# 12e.net
KiCad netlist of a schematic drawn in EAGLE
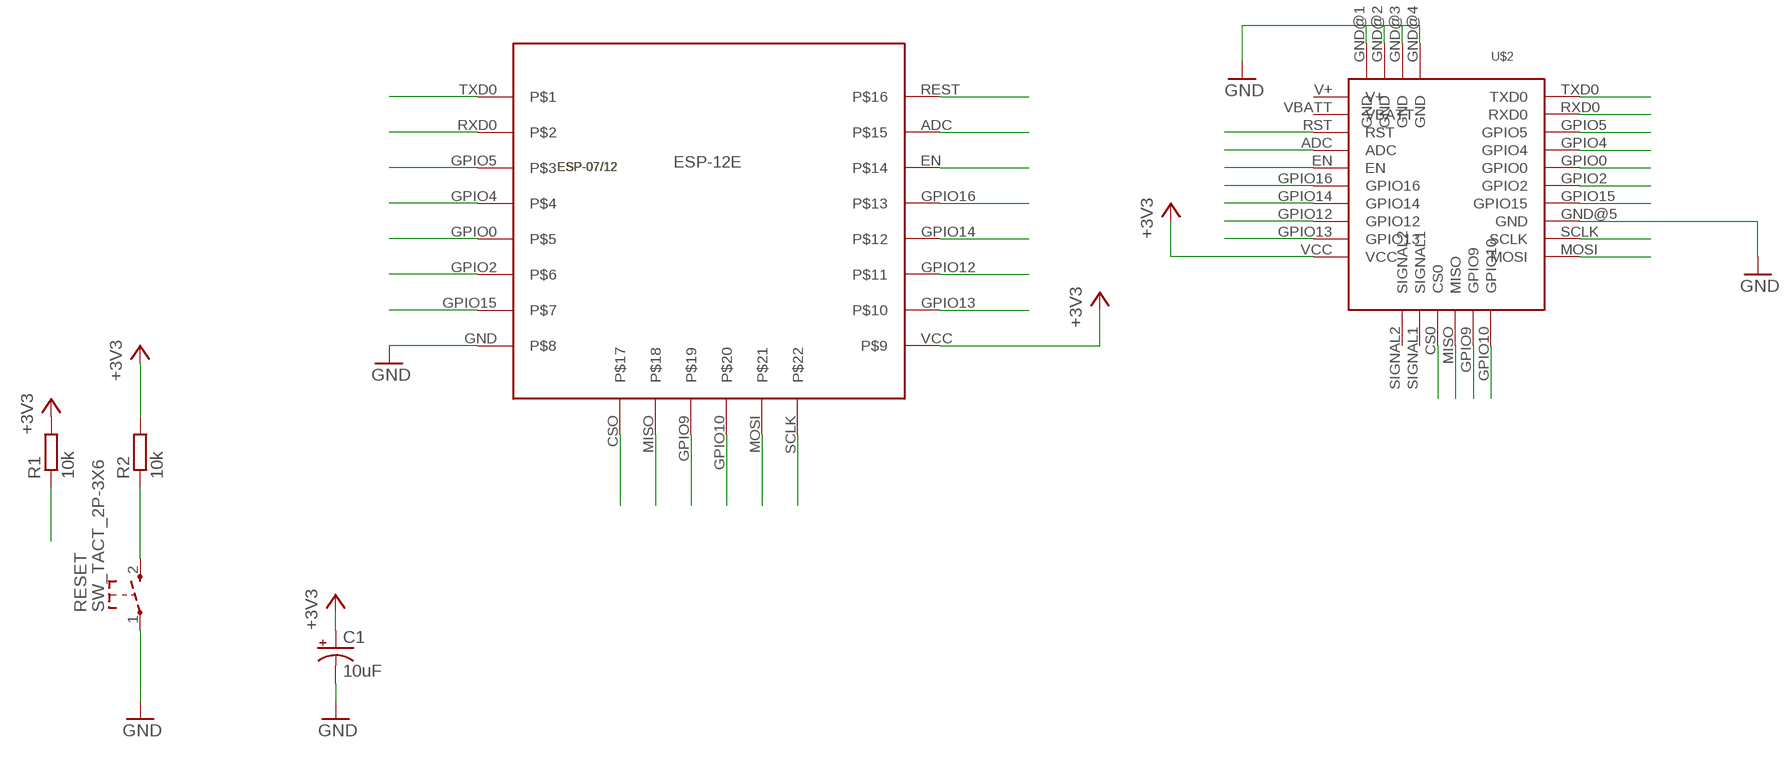
[diagram p0: schematic, sheet 1]

(export (version "E")
  (design (tool "Eeschema 10.0.6"))
  (components
    (comp (ref "C1")
      (value "10uF")
      (footprint "eagle-import:EIA3216")
      (libsource (lib "eagle-import") (part "10UF-16V-10%(TANT)"))
    )
    (comp (ref "R1")
      (value "10k")
      (footprint "eagle-import:R1206")
      (libsource (lib "eagle-import") (part "RESISTOR-1206"))
    )
    (comp (ref "R2")
      (value "10k")
      (footprint "eagle-import:R1206")
      (libsource (lib "eagle-import") (part "RESISTOR-1206"))
    )
    (comp (ref "RESET")
      (value "SW_TACT_2P-3X6")
      (footprint "eagle-import:SW_TACT_3X6")
      (libsource (lib "eagle-import") (part "SW_TACT_2P-3X6"))
    )
    (comp (ref "U$1")
      (value "ESP-07/12_ESP-12E")
      (footprint "eagle-import:ESP-07_12")
      (libsource (lib "eagle-import") (part "ESP-07/12_ESP-12E"))
    )
    (comp (ref "U$2")
      (value "ESP-BOARD")
      (footprint "eagle-import:ESP-BOARD")
      (libsource (lib "eagle-import") (part "ESP-BOARD"))
    )
  )
  (nets
    (net (code "1") (name "+3V3") (class "Default")
      (node (ref "C1") (pin "A") (pinfunction "+_A") (pintype "passive"))
      (node (ref "R1") (pin "2") (pinfunction "2_2") (pintype "passive"))
      (node (ref "R2") (pin "2") (pinfunction "2_2") (pintype "passive"))
      (node (ref "U$1") (pin "VCC") (pinfunction "P$9_VCC") (pintype "bidirectional"))
      (node (ref "U$2") (pin "VCC") (pinfunction "VCC_VCC") (pintype "power_in"))
    )
    (net (code "2") (name "/ADC") (class "Default")
      (node (ref "U$1") (pin "ADC") (pinfunction "P$15_ADC") (pintype "bidirectional"))
      (node (ref "U$2") (pin "ADC") (pinfunction "ADC_ADC") (pintype "bidirectional"))
    )
    (net (code "3") (name "/CS0") (class "Default")
      (node (ref "U$1") (pin "CSO") (pinfunction "P$17_CSO") (pintype "bidirectional"))
      (node (ref "U$2") (pin "CS0") (pinfunction "CS0_CS0") (pintype "bidirectional"))
    )
    (net (code "4") (name "/EN") (class "Default")
      (node (ref "R1") (pin "1") (pinfunction "1_1") (pintype "passive"))
      (node (ref "U$1") (pin "EN") (pinfunction "P$14_EN") (pintype "bidirectional"))
      (node (ref "U$2") (pin "EN") (pinfunction "EN_EN") (pintype "bidirectional"))
    )
    (net (code "5") (name "/GPIO0") (class "Default")
      (node (ref "U$1") (pin "GPIO0") (pinfunction "P$5_GPIO0") (pintype "bidirectional"))
      (node (ref "U$2") (pin "GPIO0") (pinfunction "GPIO0_GPIO0") (pintype "bidirectional"))
    )
    (net (code "6") (name "/GPIO2") (class "Default")
      (node (ref "U$1") (pin "GPIO2") (pinfunction "P$6_GPIO2") (pintype "bidirectional"))
      (node (ref "U$2") (pin "GPIO2") (pinfunction "GPIO2_GPIO2") (pintype "bidirectional"))
    )
    (net (code "7") (name "/GPIO4") (class "Default")
      (node (ref "U$1") (pin "GPIO4") (pinfunction "P$4_GPIO4") (pintype "bidirectional"))
      (node (ref "U$2") (pin "GPIO4") (pinfunction "GPIO4_GPIO4") (pintype "bidirectional"))
    )
    (net (code "8") (name "/GPIO5") (class "Default")
      (node (ref "U$1") (pin "GPIO5") (pinfunction "P$3_GPIO5") (pintype "bidirectional"))
      (node (ref "U$2") (pin "GPIO5") (pinfunction "GPIO5_GPIO5") (pintype "bidirectional"))
    )
    (net (code "9") (name "/GPIO9") (class "Default")
      (node (ref "U$1") (pin "GPIO9") (pinfunction "P$19_GPIO9") (pintype "bidirectional"))
      (node (ref "U$2") (pin "GPIO9") (pinfunction "GPIO9_GPIO9") (pintype "bidirectional"))
    )
    (net (code "10") (name "/GPIO10") (class "Default")
      (node (ref "U$1") (pin "GPIO10") (pinfunction "P$20_GPIO10") (pintype "bidirectional"))
      (node (ref "U$2") (pin "GPIO10") (pinfunction "GPIO10_GPIO10") (pintype "bidirectional"))
    )
    (net (code "11") (name "/GPIO12") (class "Default")
      (node (ref "U$1") (pin "GPIO12") (pinfunction "P$11_GPIO12") (pintype "bidirectional"))
      (node (ref "U$2") (pin "GPIO12") (pinfunction "GPIO12_GPIO12") (pintype "bidirectional"))
    )
    (net (code "12") (name "/GPIO13") (class "Default")
      (node (ref "U$1") (pin "GPIO13") (pinfunction "P$10_GPIO13") (pintype "bidirectional"))
      (node (ref "U$2") (pin "GPIO13") (pinfunction "GPIO13_GPIO13") (pintype "bidirectional"))
    )
    (net (code "13") (name "/GPIO14") (class "Default")
      (node (ref "U$1") (pin "GPIO14") (pinfunction "P$12_GPIO14") (pintype "bidirectional"))
      (node (ref "U$2") (pin "GPIO14") (pinfunction "GPIO14_GPIO14") (pintype "bidirectional"))
    )
    (net (code "14") (name "/GPIO15") (class "Default")
      (node (ref "U$1") (pin "GPIO15") (pinfunction "P$7_GPIO15") (pintype "bidirectional"))
      (node (ref "U$2") (pin "GPIO15") (pinfunction "GPIO15_GPIO15") (pintype "bidirectional"))
    )
    (net (code "15") (name "/GPIO16") (class "Default")
      (node (ref "U$1") (pin "GPIO16") (pinfunction "P$13_GPIO16") (pintype "bidirectional"))
      (node (ref "U$2") (pin "GPIO16") (pinfunction "GPIO16_GPIO16") (pintype "bidirectional"))
    )
    (net (code "16") (name "/MISO") (class "Default")
      (node (ref "U$1") (pin "MISO") (pinfunction "P$18_MISO") (pintype "bidirectional"))
      (node (ref "U$2") (pin "MISO") (pinfunction "MISO_MISO") (pintype "bidirectional"))
    )
    (net (code "17") (name "/MOSI") (class "Default")
      (node (ref "U$1") (pin "MOSI") (pinfunction "P$21_MOSI") (pintype "bidirectional"))
      (node (ref "U$2") (pin "MOSI") (pinfunction "MOSI_MOSI") (pintype "bidirectional"))
    )
    (net (code "18") (name "/RESET") (class "Default")
      (node (ref "R2") (pin "1") (pinfunction "1_1") (pintype "passive"))
      (node (ref "RESET") (pin "2") (pinfunction "3_2") (pintype "passive"))
      (node (ref "U$1") (pin "REST") (pinfunction "P$16_REST") (pintype "bidirectional"))
      (node (ref "U$2") (pin "RST") (pinfunction "RST_RST") (pintype "bidirectional"))
    )
    (net (code "19") (name "/RXD0") (class "Default")
      (node (ref "U$1") (pin "RXD0") (pinfunction "P$2_RXD0") (pintype "bidirectional"))
      (node (ref "U$2") (pin "RXD0") (pinfunction "RXD0_RXD0") (pintype "bidirectional"))
    )
    (net (code "20") (name "/SCLK") (class "Default")
      (node (ref "U$1") (pin "SCLK") (pinfunction "P$22_SCLK") (pintype "bidirectional"))
      (node (ref "U$2") (pin "SCLK") (pinfunction "SCLK_SCLK") (pintype "bidirectional"))
    )
    (net (code "21") (name "/TXD0") (class "Default")
      (node (ref "U$1") (pin "TXD0") (pinfunction "P$1_TXD0") (pintype "bidirectional"))
      (node (ref "U$2") (pin "TXD0") (pinfunction "TXD0_TXD0") (pintype "bidirectional"))
    )
    (net (code "22") (name "/V+") (class "Default")
      (node (ref "U$2") (pin "V+") (pinfunction "V+_V+") (pintype "power_in"))
    )
    (net (code "23") (name "/VBATT") (class "Default")
      (node (ref "U$2") (pin "VBATT") (pinfunction "VBATT_VBATT") (pintype "power_in"))
    )
    (net (code "24") (name "GND") (class "Default")
      (node (ref "C1") (pin "C") (pinfunction "-_C") (pintype "passive"))
      (node (ref "RESET") (pin "1") (pinfunction "1_1") (pintype "passive"))
      (node (ref "U$1") (pin "GND") (pinfunction "P$8_GND") (pintype "bidirectional"))
      (node (ref "U$2") (pin "GND@1") (pinfunction "GND_GND@1") (pintype "power_in"))
      (node (ref "U$2") (pin "GND@2") (pinfunction "GND_GND@2") (pintype "power_in"))
      (node (ref "U$2") (pin "GND@3") (pinfunction "GND_GND@3") (pintype "power_in"))
      (node (ref "U$2") (pin "GND@4") (pinfunction "GND_GND@4") (pintype "power_in"))
      (node (ref "U$2") (pin "GND@5") (pinfunction "GND_GND@5") (pintype "power_in"))
    )
    (net (code "25") (name "unconnected-(U$2-PadSIGNAL1)") (class "Default")
      (node (ref "U$2") (pin "SIGNAL1") (pinfunction "SIGNAL1_SIGNAL1") (pintype "bidirectional"))
    )
    (net (code "26") (name "unconnected-(U$2-PadSIGNAL2)") (class "Default")
      (node (ref "U$2") (pin "SIGNAL2") (pinfunction "SIGNAL2_SIGNAL2") (pintype "bidirectional"))
    )
  )
)
